# transmitter_by_chandan.net
KiCad netlist of a schematic drawn in EasyEDA Pro
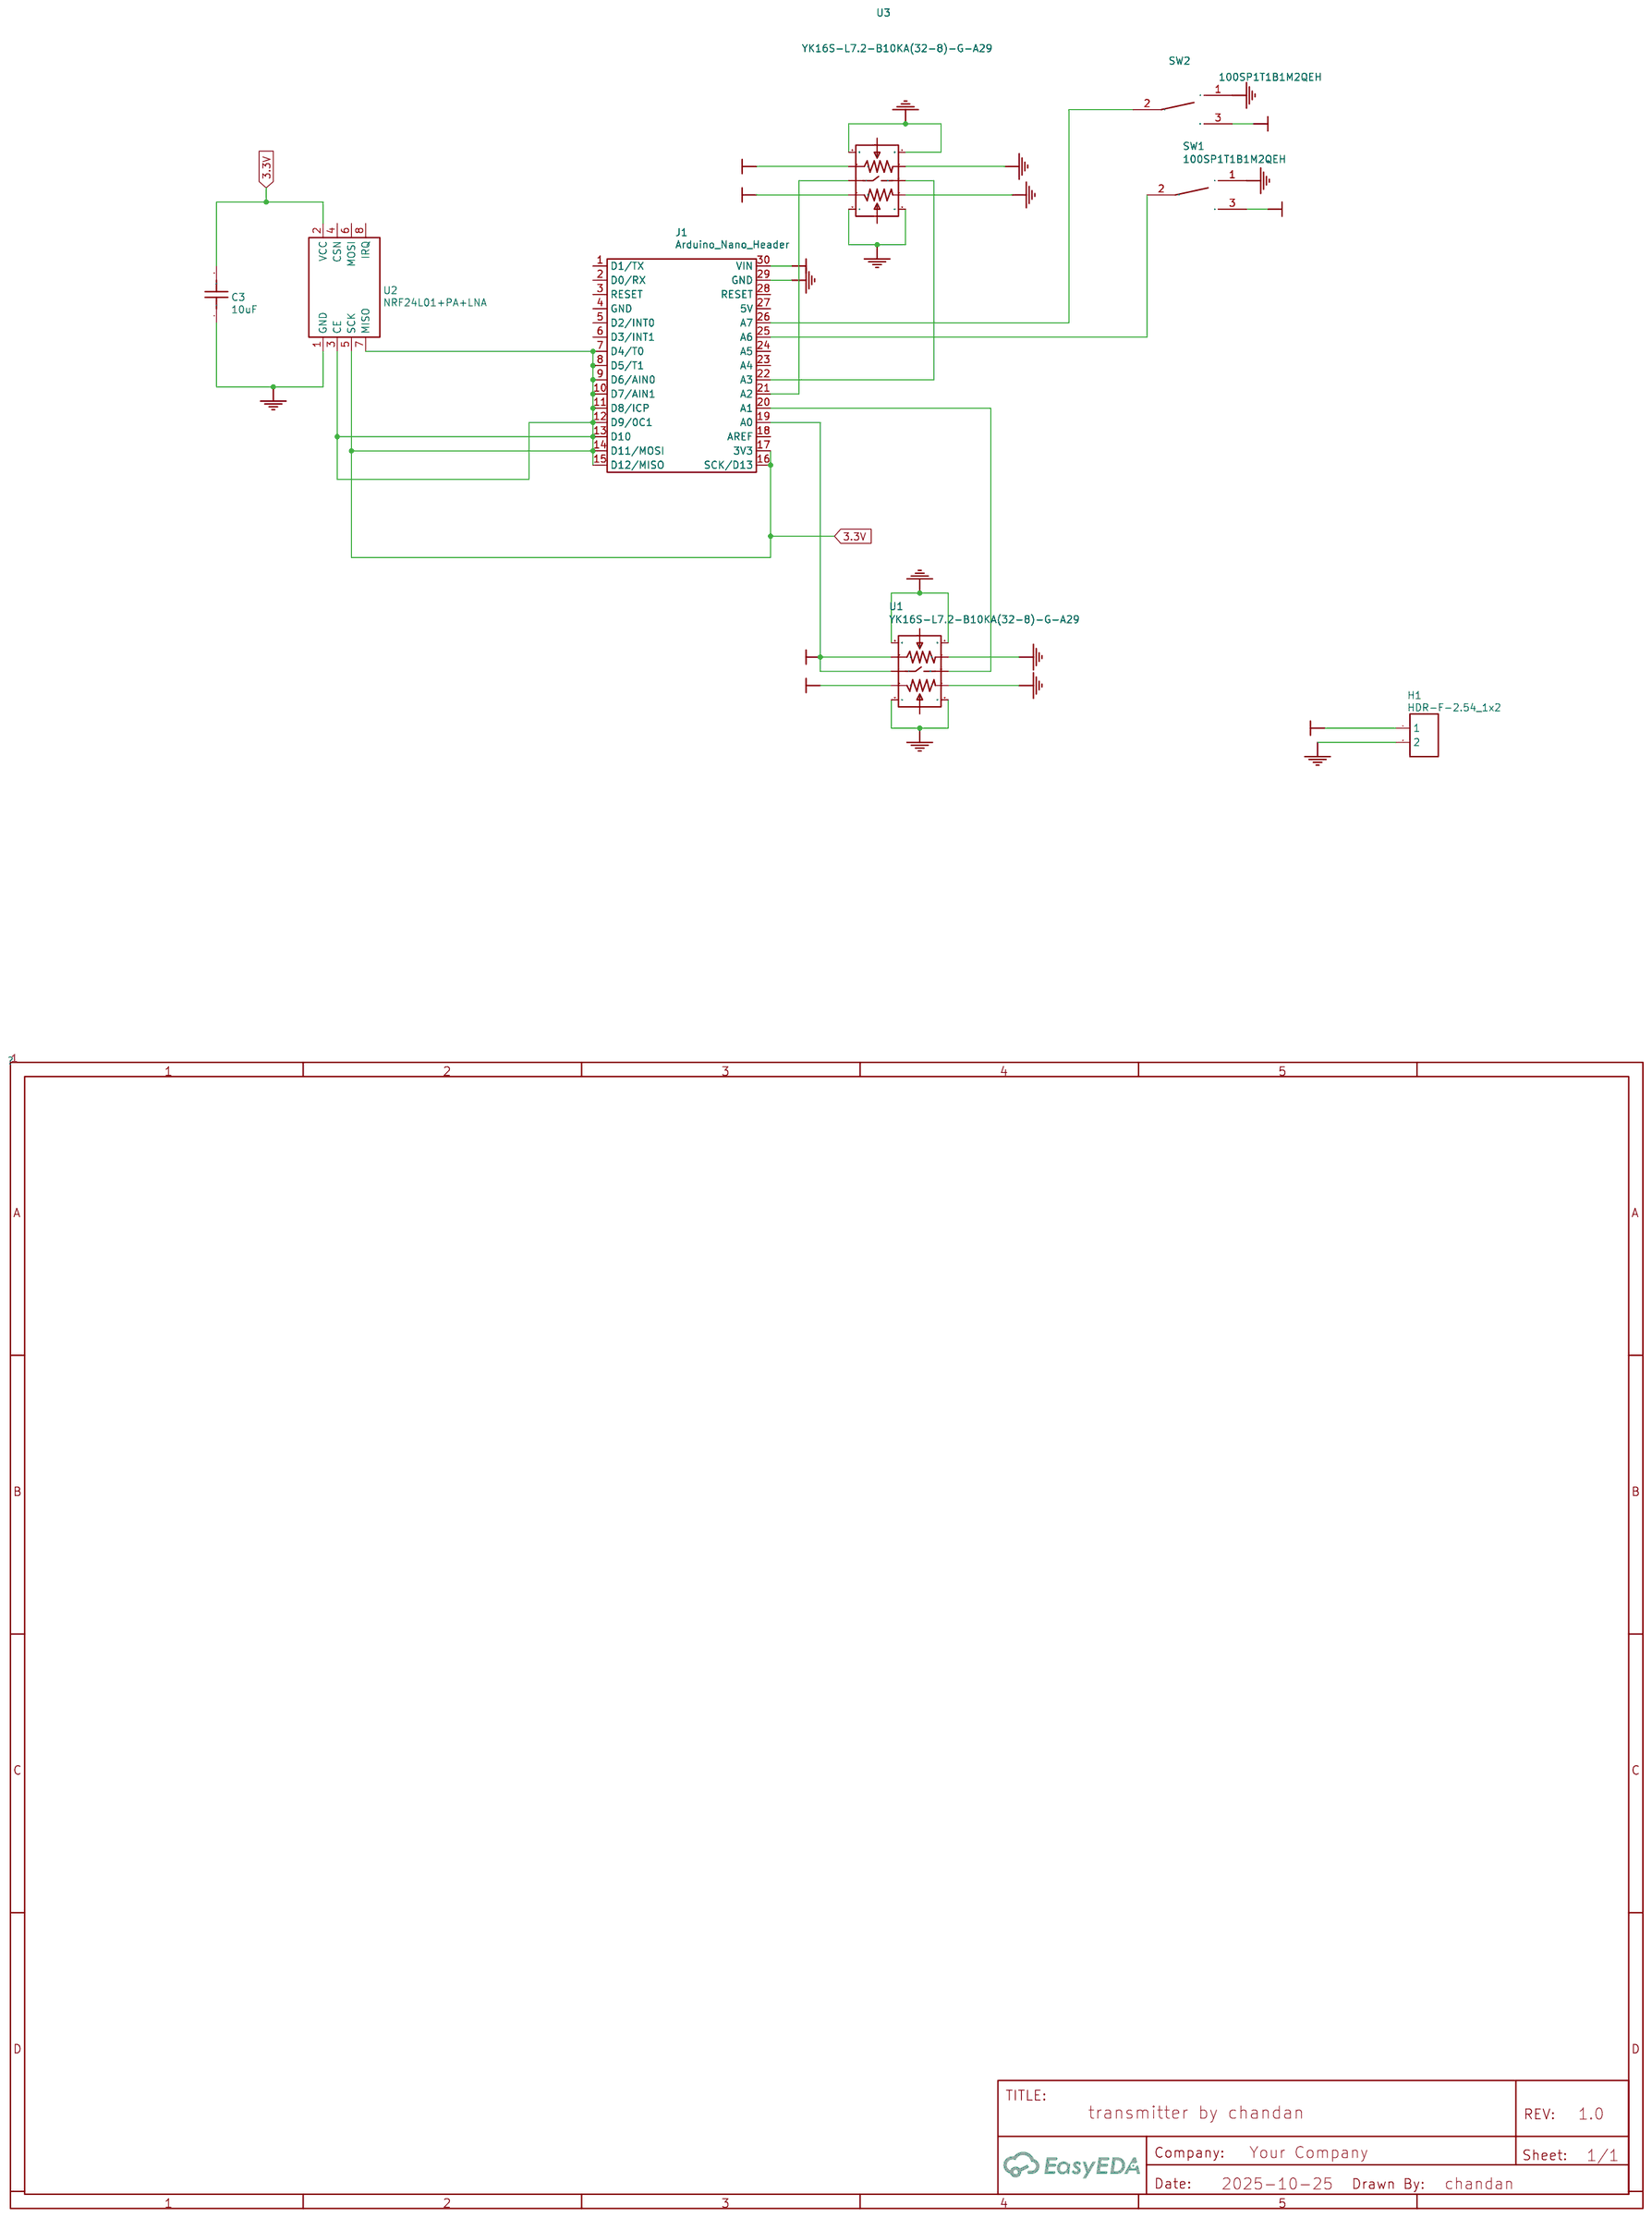
[diagram p0: schematic sheet]

(export (version "E")
  (design (tool "Eeschema 10.0.6"))
  (components
    (comp (ref "C3")
      (value "10uF")
      (fields
        (field (name "Manufacturer Part") "FK16X5R1H105K")
        (field (name "Manufacturer") "TDK")
        (field (name "Contributor") "lcsc")
      )
      (libsource (lib "easyedapro") (part "10uF"))
    )
    (comp (ref "H1")
      (value "HDR-F-2.54_1x2")
      (fields (field (name "Contributor") "LCEDA_Lib"))
      (libsource (lib "easyedapro") (part "HDR-F-2.54_1x2"))
    )
    (comp (ref "J1")
      (value "Arduino_Nano_Header")
      (libsource (lib "easyedapro") (part "Arduino_Nano_Header"))
    )
    (comp (ref "SW1")
      (value "100SP1T1B1M2QEH")
      (fields (field (name "Manufacturer") "E-Switch") (field (name "Contributor") "LCSC"))
      (libsource (lib "easyedapro") (part "100SP1T1B1M2QEH"))
    )
    (comp (ref "SW2")
      (value "100SP1T1B1M2QEH")
      (fields (field (name "Manufacturer") "E-Switch") (field (name "Contributor") "LCSC"))
      (libsource (lib "easyedapro") (part "100SP1T1B1M2QEH"))
    )
    (comp (ref "U1")
      (value "YK16S-L7.2-B10KA(32-8)-G-A29")
      (fields
        (field (name "Manufacturer Part") "YK16S-L7.2-B10Ka(32-8)-G-A29")
        (field (name "Manufacturer") "YTL(亚特联)")
        (field (name "Contributor") "lcsc")
      )
      (libsource (lib "easyedapro") (part "YK16S-L7.2-B10KA(32-8)-G-A29"))
    )
    (comp (ref "U2")
      (value "NRF24L01+PA+LNA")
      (fields (field (name "Manufacturer Part") "nRF24L01+PA+LNA") (field (name "Contributor") "lcsc"))
      (libsource (lib "easyedapro") (part "NRF24L01+PA+LNA"))
    )
    (comp (ref "U3")
      (value "YK16S-L7.2-B10KA(32-8)-G-A29")
      (fields
        (field (name "Manufacturer Part") "YK16S-L7.2-B10Ka(32-8)-G-A29")
        (field (name "Manufacturer") "YTL(亚特联)")
        (field (name "Contributor") "lcsc")
      )
      (libsource (lib "easyedapro") (part "YK16S-L7.2-B10KA(32-8)-G-A29"))
    )
  )
  (nets
    (net (code "1") (name "+5V") (class "Default")
      (node (ref "H1") (pin "1") (pinfunction "1_1") (pintype "input"))
      (node (ref "J1") (pin "19") (pinfunction "A0_19") (pintype "unspecified"))
      (node (ref "J1") (pin "30") (pinfunction "VIN_30") (pintype "unspecified"))
      (node (ref "SW1") (pin "3") (pinfunction "3_3") (pintype "input"))
      (node (ref "SW2") (pin "3") (pinfunction "3_3") (pintype "input"))
      (node (ref "U1") (pin "3") (pinfunction "3_3") (pintype "unspecified"))
      (node (ref "U1") (pin "6") (pinfunction "6_6") (pintype "unspecified"))
      (node (ref "U1") (pin "7") (pinfunction "7_7") (pintype "unspecified"))
      (node (ref "U3") (pin "3") (pinfunction "3_3") (pintype "unspecified"))
      (node (ref "U3") (pin "6") (pinfunction "6_6") (pintype "unspecified"))
    )
    (net (code "2") (name "3.3V") (class "Default")
      (node (ref "C3") (pin "2") (pinfunction "2_2") (pintype "unspecified"))
      (node (ref "J1") (pin "10") (pinfunction "D7/AIN1_10") (pintype "unspecified"))
      (node (ref "J1") (pin "11") (pinfunction "D8/ICP_11") (pintype "unspecified"))
      (node (ref "J1") (pin "12") (pinfunction "D9/0C1_12") (pintype "unspecified"))
      (node (ref "J1") (pin "13") (pinfunction "D10_13") (pintype "unspecified"))
      (node (ref "J1") (pin "14") (pinfunction "D11/MOSI_14") (pintype "unspecified"))
      (node (ref "J1") (pin "15") (pinfunction "D12/MISO_15") (pintype "unspecified"))
      (node (ref "J1") (pin "16") (pinfunction "SCK/D13_16") (pintype "unspecified"))
      (node (ref "J1") (pin "17") (pinfunction "3V3_17") (pintype "unspecified"))
      (node (ref "J1") (pin "7") (pinfunction "D4/T0_7") (pintype "unspecified"))
      (node (ref "J1") (pin "8") (pinfunction "D5/T1_8") (pintype "unspecified"))
      (node (ref "J1") (pin "9") (pinfunction "D6/AIN0_9") (pintype "unspecified"))
      (node (ref "U2") (pin "2") (pinfunction "VCC_2") (pintype "unspecified"))
      (node (ref "U2") (pin "3") (pinfunction "CE_3") (pintype "unspecified"))
      (node (ref "U2") (pin "5") (pinfunction "SCK_5") (pintype "unspecified"))
      (node (ref "U2") (pin "7") (pinfunction "MISO_7") (pintype "unspecified"))
    )
    (net (code "3") (name "GND") (class "Default")
      (node (ref "C3") (pin "1") (pinfunction "1_1") (pintype "unspecified"))
      (node (ref "H1") (pin "2") (pinfunction "2_2") (pintype "input"))
      (node (ref "J1") (pin "29") (pinfunction "GND_29") (pintype "unspecified"))
      (node (ref "SW1") (pin "1") (pinfunction "1_1") (pintype "input"))
      (node (ref "SW2") (pin "1") (pinfunction "1_1") (pintype "input"))
      (node (ref "U1") (pin "1") (pinfunction "1_1") (pintype "unspecified"))
      (node (ref "U1") (pin "10") (pinfunction "shell_10") (pintype "unspecified"))
      (node (ref "U1") (pin "11") (pinfunction "shell_11") (pintype "unspecified"))
      (node (ref "U1") (pin "12") (pinfunction "shell_12") (pintype "unspecified"))
      (node (ref "U1") (pin "4") (pinfunction "4_4") (pintype "unspecified"))
      (node (ref "U1") (pin "9") (pinfunction "shell_9") (pintype "unspecified"))
      (node (ref "U2") (pin "1") (pinfunction "GND_1") (pintype "unspecified"))
      (node (ref "U3") (pin "1") (pinfunction "1_1") (pintype "unspecified"))
      (node (ref "U3") (pin "10") (pinfunction "shell_10") (pintype "unspecified"))
      (node (ref "U3") (pin "11") (pinfunction "shell_11") (pintype "unspecified"))
      (node (ref "U3") (pin "12") (pinfunction "shell_12") (pintype "unspecified"))
      (node (ref "U3") (pin "4") (pinfunction "4_4") (pintype "unspecified"))
      (node (ref "U3") (pin "9") (pinfunction "shell_9") (pintype "unspecified"))
    )
    (net (code "4") (name "Net-(J1-A1)") (class "Default")
      (node (ref "J1") (pin "20") (pinfunction "A1_20") (pintype "unspecified"))
      (node (ref "U1") (pin "8") (pinfunction "8_8") (pintype "unspecified"))
    )
    (net (code "5") (name "Net-(J1-A2)") (class "Default")
      (node (ref "J1") (pin "21") (pinfunction "A2_21") (pintype "unspecified"))
      (node (ref "U3") (pin "7") (pinfunction "7_7") (pintype "unspecified"))
    )
    (net (code "6") (name "Net-(J1-A3)") (class "Default")
      (node (ref "J1") (pin "22") (pinfunction "A3_22") (pintype "unspecified"))
      (node (ref "U3") (pin "8") (pinfunction "8_8") (pintype "unspecified"))
    )
    (net (code "7") (name "Net-(J1-A6)") (class "Default")
      (node (ref "J1") (pin "25") (pinfunction "A6_25") (pintype "unspecified"))
      (node (ref "SW1") (pin "2") (pinfunction "2_2") (pintype "input"))
    )
    (net (code "8") (name "Net-(J1-A7)") (class "Default")
      (node (ref "J1") (pin "26") (pinfunction "A7_26") (pintype "unspecified"))
      (node (ref "SW2") (pin "2") (pinfunction "2_2") (pintype "input"))
    )
    (net (code "9") (name "unconnected-(J1-5V-Pad27)") (class "Default")
      (node (ref "J1") (pin "27") (pinfunction "5V_27") (pintype "unspecified"))
    )
    (net (code "10") (name "unconnected-(J1-A4-Pad23)") (class "Default")
      (node (ref "J1") (pin "23") (pinfunction "A4_23") (pintype "unspecified"))
    )
    (net (code "11") (name "unconnected-(J1-A5-Pad24)") (class "Default")
      (node (ref "J1") (pin "24") (pinfunction "A5_24") (pintype "unspecified"))
    )
    (net (code "12") (name "unconnected-(J1-AREF-Pad18)") (class "Default")
      (node (ref "J1") (pin "18") (pinfunction "AREF_18") (pintype "unspecified"))
    )
    (net (code "13") (name "unconnected-(J1-D0{slash}RX-Pad2)") (class "Default")
      (node (ref "J1") (pin "2") (pinfunction "D0/RX_2") (pintype "unspecified"))
    )
    (net (code "14") (name "unconnected-(J1-D1{slash}TX-Pad1)") (class "Default")
      (node (ref "J1") (pin "1") (pinfunction "D1/TX_1") (pintype "unspecified"))
    )
    (net (code "15") (name "unconnected-(J1-D2{slash}INT0-Pad5)") (class "Default")
      (node (ref "J1") (pin "5") (pinfunction "D2/INT0_5") (pintype "unspecified"))
    )
    (net (code "16") (name "unconnected-(J1-D3{slash}INT1-Pad6)") (class "Default")
      (node (ref "J1") (pin "6") (pinfunction "D3/INT1_6") (pintype "unspecified"))
    )
    (net (code "17") (name "unconnected-(J1-GND-Pad4)") (class "Default")
      (node (ref "J1") (pin "4") (pinfunction "GND_4") (pintype "unspecified"))
    )
    (net (code "18") (name "unconnected-(J1-RESET-Pad3)") (class "Default")
      (node (ref "J1") (pin "3") (pinfunction "RESET_3") (pintype "unspecified"))
    )
    (net (code "19") (name "unconnected-(J1-RESET-Pad28)") (class "Default")
      (node (ref "J1") (pin "28") (pinfunction "RESET_28") (pintype "unspecified"))
    )
    (net (code "20") (name "unconnected-(U1-Pad2)") (class "Default")
      (node (ref "U1") (pin "2") (pinfunction "2_2") (pintype "unspecified"))
    )
    (net (code "21") (name "unconnected-(U1-Pad5)") (class "Default")
      (node (ref "U1") (pin "5") (pinfunction "5_5") (pintype "unspecified"))
    )
    (net (code "22") (name "unconnected-(U2-CSN-Pad4)") (class "Default")
      (node (ref "U2") (pin "4") (pinfunction "CSN_4") (pintype "unspecified"))
    )
    (net (code "23") (name "unconnected-(U2-IRQ-Pad8)") (class "Default")
      (node (ref "U2") (pin "8") (pinfunction "IRQ_8") (pintype "unspecified"))
    )
    (net (code "24") (name "unconnected-(U2-MOSI-Pad6)") (class "Default")
      (node (ref "U2") (pin "6") (pinfunction "MOSI_6") (pintype "unspecified"))
    )
    (net (code "25") (name "unconnected-(U3-Pad2)") (class "Default")
      (node (ref "U3") (pin "2") (pinfunction "2_2") (pintype "unspecified"))
    )
    (net (code "26") (name "unconnected-(U3-Pad5)") (class "Default")
      (node (ref "U3") (pin "5") (pinfunction "5_5") (pintype "unspecified"))
    )
  )
)
